# FutureBotNanoShield.net
KiCad netlist of a schematic drawn in EAGLE
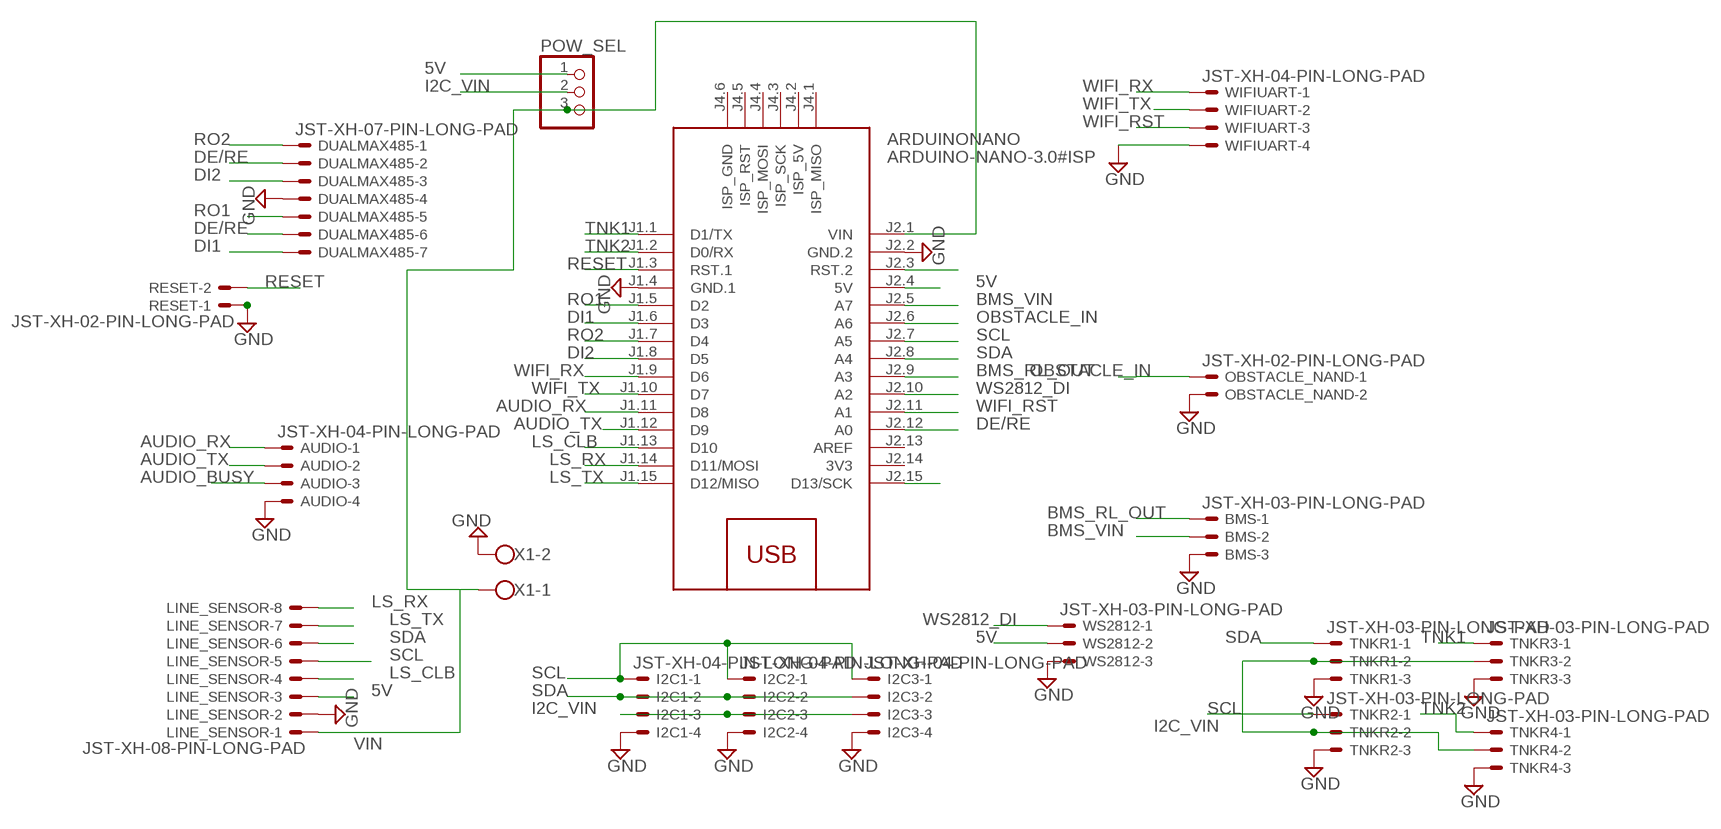
[diagram p0: schematic, sheet 1]

(export (version "E")
  (design (tool "Eeschema 10.0.6"))
  (components
    (comp (ref "ARDUINONANO")
      (value "ARDUINO-NANO-3.0#ISP")
      (footprint "eagle-import:ARDUINO-NANO-3.0#ISP")
      (libsource (lib "eagle-import") (part "ARDUINO-NANO-3.0#ISP"))
    )
    (comp (ref "AUDIO")
      (value "JST-XH-04-PIN-LONG-PAD")
      (footprint "eagle-import:JST-XH-04-PACKAGE-LONG-PAD")
      (libsource (lib "eagle-import") (part "JST-XH-04-PIN-LONG-PAD"))
    )
    (comp (ref "BMS")
      (value "JST-XH-03-PIN-LONG-PAD")
      (footprint "eagle-import:JST-XH-03-PACKAGE-LONG-PAD")
      (libsource (lib "eagle-import") (part "JST-XH-03-PIN-LONG-PAD"))
    )
    (comp (ref "DUALMAX485")
      (value "JST-XH-07-PIN-LONG-PAD")
      (footprint "eagle-import:JST-XH-07-PACKAGE-LONG-PAD")
      (libsource (lib "eagle-import") (part "JST-XH-07-PIN-LONG-PAD"))
    )
    (comp (ref "I2C1")
      (value "JST-XH-04-PIN-LONG-PAD")
      (footprint "eagle-import:JST-XH-04-PACKAGE-LONG-PAD")
      (libsource (lib "eagle-import") (part "JST-XH-04-PIN-LONG-PAD"))
    )
    (comp (ref "I2C2")
      (value "JST-XH-04-PIN-LONG-PAD")
      (footprint "eagle-import:JST-XH-04-PACKAGE-LONG-PAD")
      (libsource (lib "eagle-import") (part "JST-XH-04-PIN-LONG-PAD"))
    )
    (comp (ref "I2C3")
      (value "JST-XH-04-PIN-LONG-PAD")
      (footprint "eagle-import:JST-XH-04-PACKAGE-LONG-PAD")
      (libsource (lib "eagle-import") (part "JST-XH-04-PIN-LONG-PAD"))
    )
    (comp (ref "LINE_SENSOR")
      (value "JST-XH-08-PIN-LONG-PAD")
      (footprint "eagle-import:JST-XH-08-PACKAGE-LONG-PAD")
      (libsource (lib "eagle-import") (part "JST-XH-08-PIN-LONG-PAD"))
    )
    (comp (ref "OBSTACLE_NAND")
      (value "JST-XH-02-PIN-LONG-PAD")
      (footprint "eagle-import:JST-XH-02-PACKAGE-LONG-PAD")
      (libsource (lib "eagle-import") (part "JST-XH-02-PIN-LONG-PAD"))
    )
    (comp (ref "POW_SEL")
      (value "PINHD-1X3")
      (footprint "eagle-import:1X03")
      (libsource (lib "eagle-import") (part "PINHD-1X3"))
    )
    (comp (ref "RESET")
      (value "JST-XH-02-PIN-LONG-PAD")
      (footprint "eagle-import:JST-XH-02-PACKAGE-LONG-PAD")
      (libsource (lib "eagle-import") (part "JST-XH-02-PIN-LONG-PAD"))
    )
    (comp (ref "TNKR1")
      (value "JST-XH-03-PIN-LONG-PAD")
      (footprint "eagle-import:JST-XH-03-PACKAGE-LONG-PAD")
      (libsource (lib "eagle-import") (part "JST-XH-03-PIN-LONG-PAD"))
    )
    (comp (ref "TNKR2")
      (value "JST-XH-03-PIN-LONG-PAD")
      (footprint "eagle-import:JST-XH-03-PACKAGE-LONG-PAD")
      (libsource (lib "eagle-import") (part "JST-XH-03-PIN-LONG-PAD"))
    )
    (comp (ref "TNKR3")
      (value "JST-XH-03-PIN-LONG-PAD")
      (footprint "eagle-import:JST-XH-03-PACKAGE-LONG-PAD")
      (libsource (lib "eagle-import") (part "JST-XH-03-PIN-LONG-PAD"))
    )
    (comp (ref "TNKR4")
      (value "JST-XH-03-PIN-LONG-PAD")
      (footprint "eagle-import:JST-XH-03-PACKAGE-LONG-PAD")
      (libsource (lib "eagle-import") (part "JST-XH-03-PIN-LONG-PAD"))
    )
    (comp (ref "WIFIUART")
      (value "JST-XH-04-PIN-LONG-PAD")
      (footprint "eagle-import:JST-XH-04-PACKAGE-LONG-PAD")
      (libsource (lib "eagle-import") (part "JST-XH-04-PIN-LONG-PAD"))
    )
    (comp (ref "WS2812")
      (value "JST-XH-03-PIN-LONG-PAD")
      (footprint "eagle-import:JST-XH-03-PACKAGE-LONG-PAD")
      (libsource (lib "eagle-import") (part "JST-XH-03-PIN-LONG-PAD"))
    )
    (comp (ref "X1")
      (value "W237-102")
      (footprint "eagle-import:W237-102")
      (fields (field (name "MPN") "237-102"))
      (libsource (lib "eagle-import") (part "W237-102"))
    )
  )
  (nets
    (net (code "1") (name "/3V3") (class "Default")
      (node (ref "ARDUINONANO") (pin "J2.14") (pinfunction "3V3_J2.14") (pintype "power_in"))
    )
    (net (code "2") (name "/5V") (class "Default")
      (node (ref "ARDUINONANO") (pin "J2.4") (pinfunction "5V_J2.4") (pintype "power_in"))
      (node (ref "LINE_SENSOR") (pin "3") (pinfunction "S_3") (pintype "passive"))
      (node (ref "POW_SEL") (pin "1") (pinfunction "1_1") (pintype "passive"))
      (node (ref "WS2812") (pin "2") (pinfunction "S_2") (pintype "passive"))
    )
    (net (code "3") (name "/AUDIO_BUSY") (class "Default")
      (node (ref "AUDIO") (pin "3") (pinfunction "S_3") (pintype "passive"))
    )
    (net (code "4") (name "/AUDIO_RX") (class "Default")
      (node (ref "ARDUINONANO") (pin "J1.11") (pinfunction "D8_J1.11") (pintype "bidirectional"))
      (node (ref "AUDIO") (pin "1") (pinfunction "S_1") (pintype "passive"))
    )
    (net (code "5") (name "/AUDIO_TX") (class "Default")
      (node (ref "ARDUINONANO") (pin "J1.12") (pinfunction "D9_J1.12") (pintype "bidirectional"))
      (node (ref "AUDIO") (pin "2") (pinfunction "S_2") (pintype "passive"))
    )
    (net (code "6") (name "/BMS_RL_OUT") (class "Default")
      (node (ref "ARDUINONANO") (pin "J2.9") (pinfunction "A3_J2.9") (pintype "bidirectional"))
      (node (ref "BMS") (pin "1") (pinfunction "S_1") (pintype "passive"))
    )
    (net (code "7") (name "/BMS_VIN") (class "Default")
      (node (ref "ARDUINONANO") (pin "J2.5") (pinfunction "A7_J2.5") (pintype "bidirectional"))
      (node (ref "BMS") (pin "2") (pinfunction "S_2") (pintype "passive"))
    )
    (net (code "8") (name "/DE{slash}RE") (class "Default")
      (node (ref "ARDUINONANO") (pin "J2.12") (pinfunction "A0_J2.12") (pintype "bidirectional"))
      (node (ref "DUALMAX485") (pin "2") (pinfunction "S_2") (pintype "passive"))
      (node (ref "DUALMAX485") (pin "6") (pinfunction "S_6") (pintype "passive"))
    )
    (net (code "9") (name "/DI1") (class "Default")
      (node (ref "ARDUINONANO") (pin "J1.6") (pinfunction "D3_J1.6") (pintype "bidirectional"))
      (node (ref "DUALMAX485") (pin "7") (pinfunction "S_7") (pintype "passive"))
    )
    (net (code "10") (name "/DI2") (class "Default")
      (node (ref "ARDUINONANO") (pin "J1.8") (pinfunction "D5_J1.8") (pintype "bidirectional"))
      (node (ref "DUALMAX485") (pin "3") (pinfunction "S_3") (pintype "passive"))
    )
    (net (code "11") (name "/I2C_VIN") (class "Default")
      (node (ref "I2C1") (pin "3") (pinfunction "S_3") (pintype "passive"))
      (node (ref "I2C2") (pin "3") (pinfunction "S_3") (pintype "passive"))
      (node (ref "I2C3") (pin "3") (pinfunction "S_3") (pintype "passive"))
      (node (ref "POW_SEL") (pin "2") (pinfunction "2_2") (pintype "passive"))
      (node (ref "TNKR1") (pin "2") (pinfunction "S_2") (pintype "passive"))
      (node (ref "TNKR2") (pin "2") (pinfunction "S_2") (pintype "passive"))
      (node (ref "TNKR3") (pin "2") (pinfunction "S_2") (pintype "passive"))
      (node (ref "TNKR4") (pin "2") (pinfunction "S_2") (pintype "passive"))
    )
    (net (code "12") (name "/LS_CLB") (class "Default")
      (node (ref "ARDUINONANO") (pin "J1.13") (pinfunction "D10_J1.13") (pintype "bidirectional"))
      (node (ref "LINE_SENSOR") (pin "4") (pinfunction "S_4") (pintype "passive"))
    )
    (net (code "13") (name "/LS_RX") (class "Default")
      (node (ref "ARDUINONANO") (pin "J1.14") (pinfunction "D11/MOSI_J1.14") (pintype "bidirectional"))
      (node (ref "LINE_SENSOR") (pin "8") (pinfunction "S_8") (pintype "passive"))
    )
    (net (code "14") (name "/LS_TX") (class "Default")
      (node (ref "ARDUINONANO") (pin "J1.15") (pinfunction "D12/MISO_J1.15") (pintype "bidirectional"))
      (node (ref "LINE_SENSOR") (pin "7") (pinfunction "S_7") (pintype "passive"))
    )
    (net (code "15") (name "/OBSTACLE_IN") (class "Default")
      (node (ref "ARDUINONANO") (pin "J2.6") (pinfunction "A6_J2.6") (pintype "bidirectional"))
      (node (ref "OBSTACLE_NAND") (pin "1") (pinfunction "S_1") (pintype "passive"))
    )
    (net (code "16") (name "/RESET") (class "Default")
      (node (ref "ARDUINONANO") (pin "J1.3") (pinfunction "RST.1_J1.3") (pintype "bidirectional"))
      (node (ref "RESET") (pin "2") (pinfunction "S_2") (pintype "passive"))
    )
    (net (code "17") (name "/RO1") (class "Default")
      (node (ref "ARDUINONANO") (pin "J1.5") (pinfunction "D2_J1.5") (pintype "bidirectional"))
      (node (ref "DUALMAX485") (pin "5") (pinfunction "S_5") (pintype "passive"))
    )
    (net (code "18") (name "/RO2") (class "Default")
      (node (ref "ARDUINONANO") (pin "J1.7") (pinfunction "D4_J1.7") (pintype "bidirectional"))
      (node (ref "DUALMAX485") (pin "1") (pinfunction "S_1") (pintype "passive"))
    )
    (net (code "19") (name "/SCL") (class "Default")
      (node (ref "ARDUINONANO") (pin "J2.7") (pinfunction "A5_J2.7") (pintype "bidirectional"))
      (node (ref "I2C1") (pin "1") (pinfunction "S_1") (pintype "passive"))
      (node (ref "I2C2") (pin "1") (pinfunction "S_1") (pintype "passive"))
      (node (ref "I2C3") (pin "1") (pinfunction "S_1") (pintype "passive"))
      (node (ref "LINE_SENSOR") (pin "5") (pinfunction "S_5") (pintype "passive"))
      (node (ref "TNKR2") (pin "1") (pinfunction "S_1") (pintype "passive"))
    )
    (net (code "20") (name "/SDA") (class "Default")
      (node (ref "ARDUINONANO") (pin "J2.8") (pinfunction "A4_J2.8") (pintype "bidirectional"))
      (node (ref "I2C1") (pin "2") (pinfunction "S_2") (pintype "passive"))
      (node (ref "I2C2") (pin "2") (pinfunction "S_2") (pintype "passive"))
      (node (ref "I2C3") (pin "2") (pinfunction "S_2") (pintype "passive"))
      (node (ref "LINE_SENSOR") (pin "6") (pinfunction "S_6") (pintype "passive"))
      (node (ref "TNKR1") (pin "1") (pinfunction "S_1") (pintype "passive"))
    )
    (net (code "21") (name "/TNK1") (class "Default")
      (node (ref "ARDUINONANO") (pin "J1.1") (pinfunction "D1/TX_J1.1") (pintype "bidirectional"))
      (node (ref "TNKR3") (pin "1") (pinfunction "S_1") (pintype "passive"))
    )
    (net (code "22") (name "/TNK2") (class "Default")
      (node (ref "ARDUINONANO") (pin "J1.2") (pinfunction "D0/RX_J1.2") (pintype "bidirectional"))
      (node (ref "TNKR4") (pin "1") (pinfunction "S_1") (pintype "passive"))
    )
    (net (code "23") (name "/VIN") (class "Default")
      (node (ref "ARDUINONANO") (pin "J2.1") (pinfunction "VIN_J2.1") (pintype "power_in"))
      (node (ref "LINE_SENSOR") (pin "1") (pinfunction "S_1") (pintype "passive"))
      (node (ref "POW_SEL") (pin "3") (pinfunction "3_3") (pintype "passive"))
      (node (ref "X1") (pin "1") (pinfunction "KL_1") (pintype "passive"))
    )
    (net (code "24") (name "/WIFI_RST") (class "Default")
      (node (ref "ARDUINONANO") (pin "J2.11") (pinfunction "A1_J2.11") (pintype "bidirectional"))
      (node (ref "WIFIUART") (pin "3") (pinfunction "S_3") (pintype "passive"))
    )
    (net (code "25") (name "/WIFI_RX") (class "Default")
      (node (ref "ARDUINONANO") (pin "J1.9") (pinfunction "D6_J1.9") (pintype "bidirectional"))
      (node (ref "WIFIUART") (pin "1") (pinfunction "S_1") (pintype "passive"))
    )
    (net (code "26") (name "/WIFI_TX") (class "Default")
      (node (ref "ARDUINONANO") (pin "J1.10") (pinfunction "D7_J1.10") (pintype "bidirectional"))
      (node (ref "WIFIUART") (pin "2") (pinfunction "S_2") (pintype "passive"))
    )
    (net (code "27") (name "/WS2812_DI") (class "Default")
      (node (ref "ARDUINONANO") (pin "J2.10") (pinfunction "A2_J2.10") (pintype "bidirectional"))
      (node (ref "WS2812") (pin "1") (pinfunction "S_1") (pintype "passive"))
    )
    (net (code "28") (name "GND") (class "Default")
      (node (ref "ARDUINONANO") (pin "J1.4") (pinfunction "GND.1_J1.4") (pintype "power_in"))
      (node (ref "ARDUINONANO") (pin "J2.2") (pinfunction "GND.2_J2.2") (pintype "power_in"))
      (node (ref "AUDIO") (pin "4") (pinfunction "S_4") (pintype "passive"))
      (node (ref "BMS") (pin "3") (pinfunction "S_3") (pintype "passive"))
      (node (ref "DUALMAX485") (pin "4") (pinfunction "S_4") (pintype "passive"))
      (node (ref "I2C1") (pin "4") (pinfunction "S_4") (pintype "passive"))
      (node (ref "I2C2") (pin "4") (pinfunction "S_4") (pintype "passive"))
      (node (ref "I2C3") (pin "4") (pinfunction "S_4") (pintype "passive"))
      (node (ref "LINE_SENSOR") (pin "2") (pinfunction "S_2") (pintype "passive"))
      (node (ref "OBSTACLE_NAND") (pin "2") (pinfunction "S_2") (pintype "passive"))
      (node (ref "RESET") (pin "1") (pinfunction "S_1") (pintype "passive"))
      (node (ref "TNKR1") (pin "3") (pinfunction "S_3") (pintype "passive"))
      (node (ref "TNKR2") (pin "3") (pinfunction "S_3") (pintype "passive"))
      (node (ref "TNKR3") (pin "3") (pinfunction "S_3") (pintype "passive"))
      (node (ref "TNKR4") (pin "3") (pinfunction "S_3") (pintype "passive"))
      (node (ref "WIFIUART") (pin "4") (pinfunction "S_4") (pintype "passive"))
      (node (ref "WS2812") (pin "3") (pinfunction "S_3") (pintype "passive"))
      (node (ref "X1") (pin "2") (pinfunction "KL_2") (pintype "passive"))
    )
    (net (code "29") (name "unconnected-(ARDUINONANO-AREF-PadJ2.13)") (class "Default")
      (node (ref "ARDUINONANO") (pin "J2.13") (pinfunction "AREF_J2.13") (pintype "bidirectional"))
    )
    (net (code "30") (name "unconnected-(ARDUINONANO-D13{slash}SCK-PadJ2.15)") (class "Default")
      (node (ref "ARDUINONANO") (pin "J2.15") (pinfunction "D13/SCK_J2.15") (pintype "bidirectional"))
    )
    (net (code "31") (name "unconnected-(ARDUINONANO-ISP_5V-PadJ4.2)") (class "Default")
      (node (ref "ARDUINONANO") (pin "J4.2") (pinfunction "ISP_5V_J4.2") (pintype "bidirectional"))
    )
    (net (code "32") (name "unconnected-(ARDUINONANO-ISP_GND-PadJ4.6)") (class "Default")
      (node (ref "ARDUINONANO") (pin "J4.6") (pinfunction "ISP_GND_J4.6") (pintype "bidirectional"))
    )
    (net (code "33") (name "unconnected-(ARDUINONANO-ISP_MISO-PadJ4.1)") (class "Default")
      (node (ref "ARDUINONANO") (pin "J4.1") (pinfunction "ISP_MISO_J4.1") (pintype "bidirectional"))
    )
    (net (code "34") (name "unconnected-(ARDUINONANO-ISP_MOSI-PadJ4.4)") (class "Default")
      (node (ref "ARDUINONANO") (pin "J4.4") (pinfunction "ISP_MOSI_J4.4") (pintype "bidirectional"))
    )
    (net (code "35") (name "unconnected-(ARDUINONANO-ISP_RST-PadJ4.5)") (class "Default")
      (node (ref "ARDUINONANO") (pin "J4.5") (pinfunction "ISP_RST_J4.5") (pintype "bidirectional"))
    )
    (net (code "36") (name "unconnected-(ARDUINONANO-ISP_SCK-PadJ4.3)") (class "Default")
      (node (ref "ARDUINONANO") (pin "J4.3") (pinfunction "ISP_SCK_J4.3") (pintype "bidirectional"))
    )
    (net (code "37") (name "unconnected-(ARDUINONANO-RST.2-PadJ2.3)") (class "Default")
      (node (ref "ARDUINONANO") (pin "J2.3") (pinfunction "RST.2_J2.3") (pintype "bidirectional"))
    )
  )
)
